# ArduitsyR2.net
KiCad netlist of a schematic drawn in EAGLE
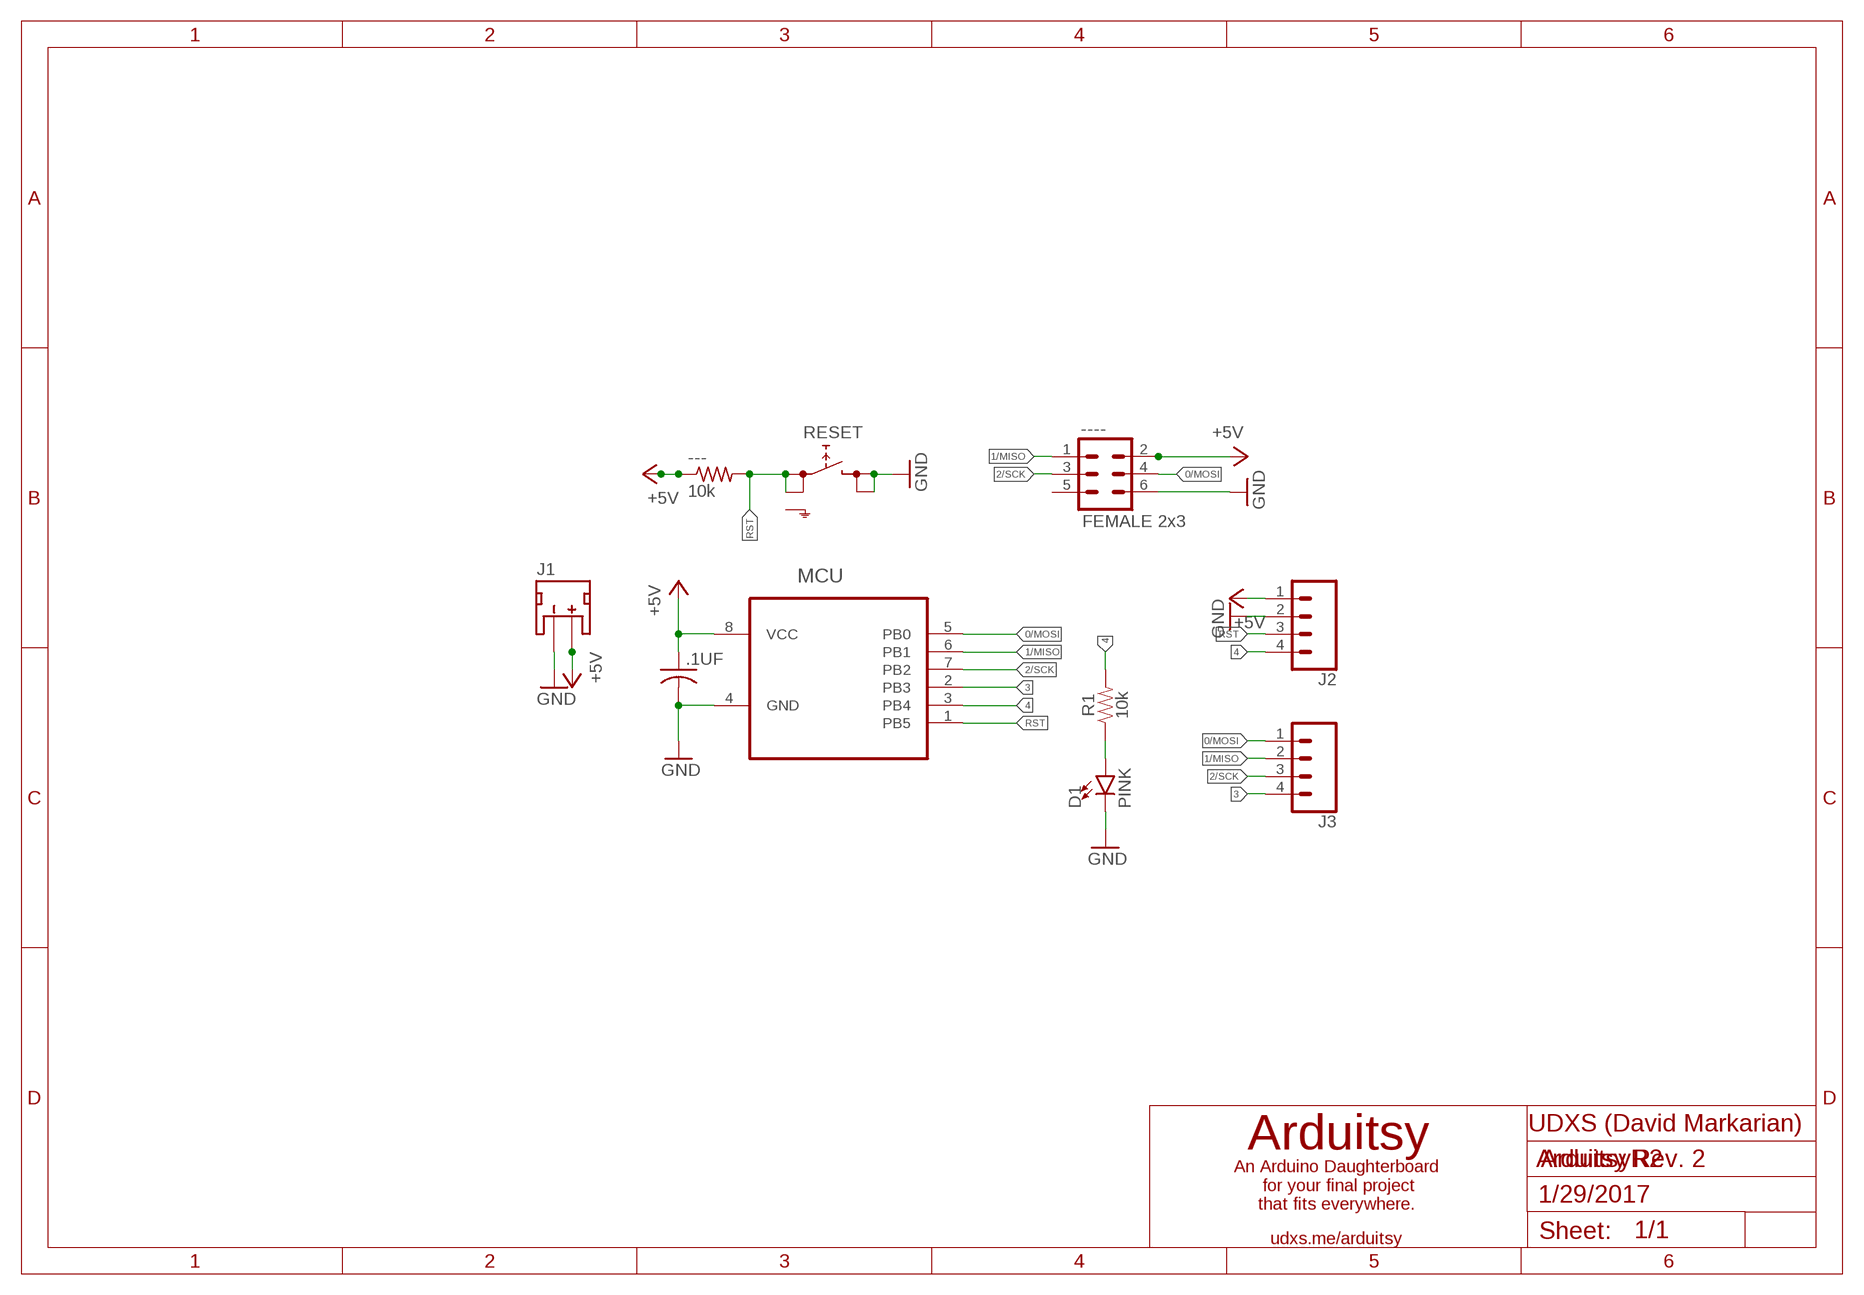
[diagram p0: schematic, sheet 1]

(export (version "E")
  (design (tool "Eeschema 10.0.6"))
  (components
    (comp (ref "---")
      (value "10k")
      (footprint "eagle-import:M0805")
      (libsource (lib "eagle-import") (part "R-US_M0805"))
    )
    (comp (ref "----")
      (value "FEMALE 2x3")
      (footprint "eagle-import:2X3")
      (libsource (lib "eagle-import") (part "CONN_03X2FEMALE"))
    )
    (comp (ref ".1UF")
      (value "C-USC0805")
      (footprint "eagle-import:C0805")
      (libsource (lib "eagle-import") (part "C-USC0805"))
    )
    (comp (ref "D1")
      (value "PINK")
      (footprint "eagle-import:LED-1206")
      (libsource (lib "eagle-import") (part "LED-PINK1206"))
    )
    (comp (ref "J1")
      (value "+5V")
      (footprint "eagle-import:JST-2-SMD")
      (libsource (lib "eagle-import") (part "JST_2MM_MALE"))
    )
    (comp (ref "J2")
      (value "CONN_04")
      (footprint "eagle-import:1X04")
      (libsource (lib "eagle-import") (part "CONN_04"))
    )
    (comp (ref "J3")
      (value "CONN_04")
      (footprint "eagle-import:1X04")
      (libsource (lib "eagle-import") (part "CONN_04"))
    )
    (comp (ref "MCU")
      (value "ATTINY85-20SU")
      (footprint "eagle-import:SOIC127P798X216-8N")
      (libsource (lib "eagle-import") (part "ATTINY85-20SU"))
    )
    (comp (ref "R1")
      (value "10k")
      (footprint "eagle-import:0603")
      (libsource (lib "eagle-import") (part "10KOHM-0603-1/10W-1%"))
    )
    (comp (ref "RESET")
      (value "SKHMPSE010")
      (footprint "eagle-import:SKHMPXE010")
      (libsource (lib "eagle-import") (part "SKHMPE010S"))
    )
  )
  (nets
    (net (code "1") (name "+5V") (class "Default")
      (node (ref "---") (pin "1") (pinfunction "1_1") (pintype "passive"))
      (node (ref "----") (pin "2") (pinfunction "2_2") (pintype "bidirectional"))
      (node (ref ".1UF") (pin "1") (pinfunction "1_1") (pintype "passive"))
      (node (ref "J1") (pin "2") (pinfunction "+_2") (pintype "bidirectional"))
      (node (ref "J2") (pin "1") (pinfunction "1_1") (pintype "passive"))
      (node (ref "MCU") (pin "8") (pinfunction "VCC_8") (pintype "power_in"))
    )
    (net (code "2") (name "0{slash}MOSI") (class "Default")
      (node (ref "----") (pin "4") (pinfunction "4_4") (pintype "bidirectional"))
      (node (ref "J3") (pin "1") (pinfunction "1_1") (pintype "passive"))
      (node (ref "MCU") (pin "5") (pinfunction "PB0_5") (pintype "bidirectional"))
    )
    (net (code "3") (name "1{slash}MISO") (class "Default")
      (node (ref "----") (pin "1") (pinfunction "1_1") (pintype "bidirectional"))
      (node (ref "J3") (pin "2") (pinfunction "2_2") (pintype "passive"))
      (node (ref "MCU") (pin "6") (pinfunction "PB1_6") (pintype "bidirectional"))
    )
    (net (code "4") (name "2{slash}SCK") (class "Default")
      (node (ref "----") (pin "3") (pinfunction "3_3") (pintype "bidirectional"))
      (node (ref "J3") (pin "3") (pinfunction "3_3") (pintype "passive"))
      (node (ref "MCU") (pin "7") (pinfunction "PB2_7") (pintype "bidirectional"))
    )
    (net (code "5") (name "3") (class "Default")
      (node (ref "J3") (pin "4") (pinfunction "4_4") (pintype "passive"))
      (node (ref "MCU") (pin "2") (pinfunction "PB3_2") (pintype "bidirectional"))
    )
    (net (code "6") (name "4") (class "Default")
      (node (ref "J2") (pin "4") (pinfunction "4_4") (pintype "passive"))
      (node (ref "MCU") (pin "3") (pinfunction "PB4_3") (pintype "bidirectional"))
      (node (ref "R1") (pin "2") (pinfunction "2_2") (pintype "passive"))
    )
    (net (code "7") (name "GND") (class "Default")
      (node (ref "----") (pin "6") (pinfunction "6_6") (pintype "bidirectional"))
      (node (ref ".1UF") (pin "2") (pinfunction "2_2") (pintype "passive"))
      (node (ref "D1") (pin "C") (pinfunction "C_C") (pintype "passive"))
      (node (ref "J1") (pin "1") (pinfunction "-_1") (pintype "bidirectional"))
      (node (ref "J2") (pin "2") (pinfunction "2_2") (pintype "passive"))
      (node (ref "MCU") (pin "4") (pinfunction "GND_4") (pintype "passive"))
      (node (ref "RESET") (pin "3") (pinfunction "2.1_3") (pintype "passive"))
      (node (ref "RESET") (pin "4") (pinfunction "2.2_4") (pintype "passive"))
    )
    (net (code "8") (name "Net-(D1-PadA)") (class "Default")
      (node (ref "D1") (pin "A") (pinfunction "A_A") (pintype "passive"))
      (node (ref "R1") (pin "1") (pinfunction "1_1") (pintype "passive"))
    )
    (net (code "9") (name "RST") (class "Default")
      (node (ref "---") (pin "2") (pinfunction "2_2") (pintype "passive"))
      (node (ref "J2") (pin "3") (pinfunction "3_3") (pintype "passive"))
      (node (ref "MCU") (pin "1") (pinfunction "PB5_1") (pintype "bidirectional"))
      (node (ref "RESET") (pin "1") (pinfunction "1.1_1") (pintype "passive"))
      (node (ref "RESET") (pin "2") (pinfunction "1.2_2") (pintype "passive"))
    )
    (net (code "10") (name "unconnected-(-----Pad5)") (class "Default")
      (node (ref "----") (pin "5") (pinfunction "5_5") (pintype "bidirectional"))
    )
    (net (code "11") (name "unconnected-(J1-PAD1-PadNC1)") (class "Default")
      (node (ref "J1") (pin "NC1") (pinfunction "PAD1_NC1") (pintype "bidirectional"))
    )
    (net (code "12") (name "unconnected-(J1-PAD2-PadNC2)") (class "Default")
      (node (ref "J1") (pin "NC2") (pinfunction "PAD2_NC2") (pintype "bidirectional"))
    )
    (net (code "13") (name "unconnected-(RESET-SH-Pad5)") (class "Default")
      (node (ref "RESET") (pin "5") (pinfunction "SH_5") (pintype "passive"))
    )
  )
)
